# OpAmp.net
KiCad netlist of a schematic drawn in Altium Designer
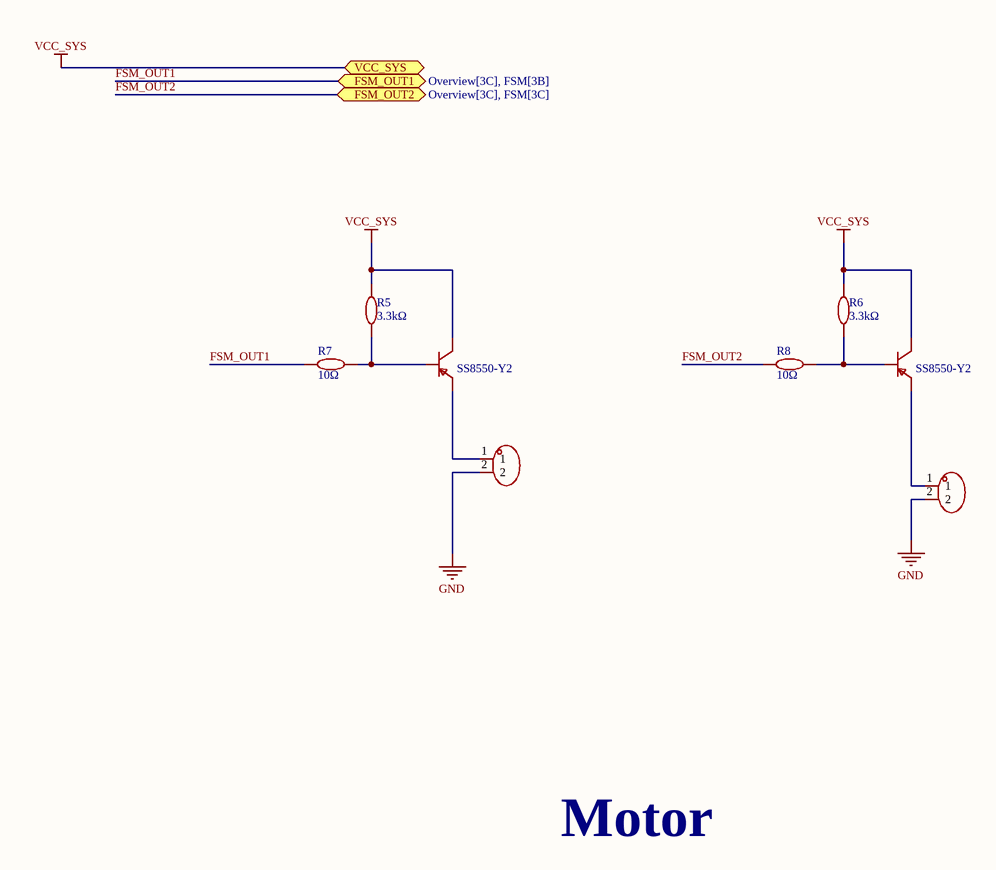
[diagram p0: OpAmp.SchDoc]

(export (version "E")
  (design (tool "Eeschema 10.0.6"))
  (components
    (comp (ref "Q1")
      (value "SS8550-Y2")
      (footprint "SOT-23_L2.9-W1.3-P1.90-LS2.4-BR")
      (description "H档200-350 PNP 电流:1.5A 电压:25V 该 PNP 双极晶体管适用于线性和开关应用。此器件采用 SOT-23 封装，适用于低功率表面贴装应用。")
      (libsource (lib "Transistor") (part "SS8550-Y2"))
    )
    (comp (ref "Q2")
      (value "SS8550-Y2")
      (footprint "SOT-23_L2.9-W1.3-P1.90-LS2.4-BR")
      (description "H档200-350 PNP 电流:1.5A 电压:25V 该 PNP 双极晶体管适用于线性和开关应用。此器件采用 SOT-23 封装，适用于低功率表面贴装应用。")
      (libsource (lib "Transistor") (part "SS8550-Y2"))
    )
    (comp (ref "R5")
      (value "3.3kΩ")
      (footprint "R0402")
      (description "62.5mW 3.3kΩ 50V ±100ppm/℃ Thick Film Resistor ±1% 0402 Chip Resistor - Surface Mount ROHS")
      (libsource (lib "RLC") (part "3.3kΩ"))
    )
    (comp (ref "R6")
      (value "3.3kΩ")
      (footprint "R0402")
      (description "62.5mW 3.3kΩ 50V ±100ppm/℃ Thick Film Resistor ±1% 0402 Chip Resistor - Surface Mount ROHS")
      (libsource (lib "RLC") (part "3.3kΩ"))
    )
    (comp (ref "R7")
      (value "10Ω")
      (footprint "R0402")
      (description "10Ω 62.5mW 50V ±200ppm/℃ Thick Film Resistor ±1% 0402 Chip Resistor - Surface Mount ROHS")
      (libsource (lib "RLC") (part "10Ω"))
    )
    (comp (ref "R8")
      (value "10Ω")
      (footprint "R0402")
      (description "10Ω 62.5mW 50V ±200ppm/℃ Thick Film Resistor ±1% 0402 Chip Resistor - Surface Mount ROHS")
      (libsource (lib "RLC") (part "10Ω"))
    )
    (comp (ref "U7")
      (value "WJ500V-5.08-2P-13-00A")
      (footprint "CONN-TH_DB125-2.54-2P-GN")
      (description "2.54 srew terminal")
      (fields (field (name "MANUFACTURER") "KANGNEX(康奈克斯电气)"))
      (libsource (lib "Connector") (part "DORABO DB125-2.54-2P-GN-S"))
    )
    (comp (ref "U8")
      (value "WJ500V-5.08-2P-13-00A")
      (footprint "CONN-TH_DB125-2.54-2P-GN")
      (description "2.54 srew terminal")
      (fields (field (name "MANUFACTURER") "KANGNEX(康奈克斯电气)"))
      (libsource (lib "Connector") (part "DORABO DB125-2.54-2P-GN-S"))
    )
  )
  (nets
    (net (code "1") (name "/FSM_OUT1") (class "Default")
      (node (ref "R7") (pin "1") (pinfunction "1_1") (pintype "passive"))
    )
    (net (code "2") (name "/FSM_OUT2") (class "Default")
      (node (ref "R8") (pin "1") (pinfunction "1_1") (pintype "passive"))
    )
    (net (code "3") (name "GND") (class "Default")
      (node (ref "U7") (pin "2") (pinfunction "2_2") (pintype "passive"))
      (node (ref "U8") (pin "2") (pinfunction "2_2") (pintype "passive"))
    )
    (net (code "4") (name "Net-(Q1-B)") (class "Default")
      (node (ref "Q1") (pin "1") (pinfunction "B_1") (pintype "passive"))
      (node (ref "R5") (pin "1") (pinfunction "1_1") (pintype "passive"))
      (node (ref "R7") (pin "2") (pinfunction "2_2") (pintype "passive"))
    )
    (net (code "5") (name "Net-(Q1-E)") (class "Default")
      (node (ref "Q1") (pin "2") (pinfunction "E_2") (pintype "passive"))
      (node (ref "U7") (pin "1") (pinfunction "1_1") (pintype "passive"))
    )
    (net (code "6") (name "Net-(Q2-B)") (class "Default")
      (node (ref "Q2") (pin "1") (pinfunction "B_1") (pintype "passive"))
      (node (ref "R6") (pin "1") (pinfunction "1_1") (pintype "passive"))
      (node (ref "R8") (pin "2") (pinfunction "2_2") (pintype "passive"))
    )
    (net (code "7") (name "Net-(Q2-E)") (class "Default")
      (node (ref "Q2") (pin "2") (pinfunction "E_2") (pintype "passive"))
      (node (ref "U8") (pin "1") (pinfunction "1_1") (pintype "passive"))
    )
    (net (code "8") (name "VCC_SYS") (class "Default")
      (node (ref "Q1") (pin "3") (pinfunction "C_3") (pintype "passive"))
      (node (ref "Q2") (pin "3") (pinfunction "C_3") (pintype "passive"))
      (node (ref "R5") (pin "2") (pinfunction "2_2") (pintype "passive"))
      (node (ref "R6") (pin "2") (pinfunction "2_2") (pintype "passive"))
    )
  )
)
